# design.net
KiCad netlist of a schematic drawn in Altium Designer
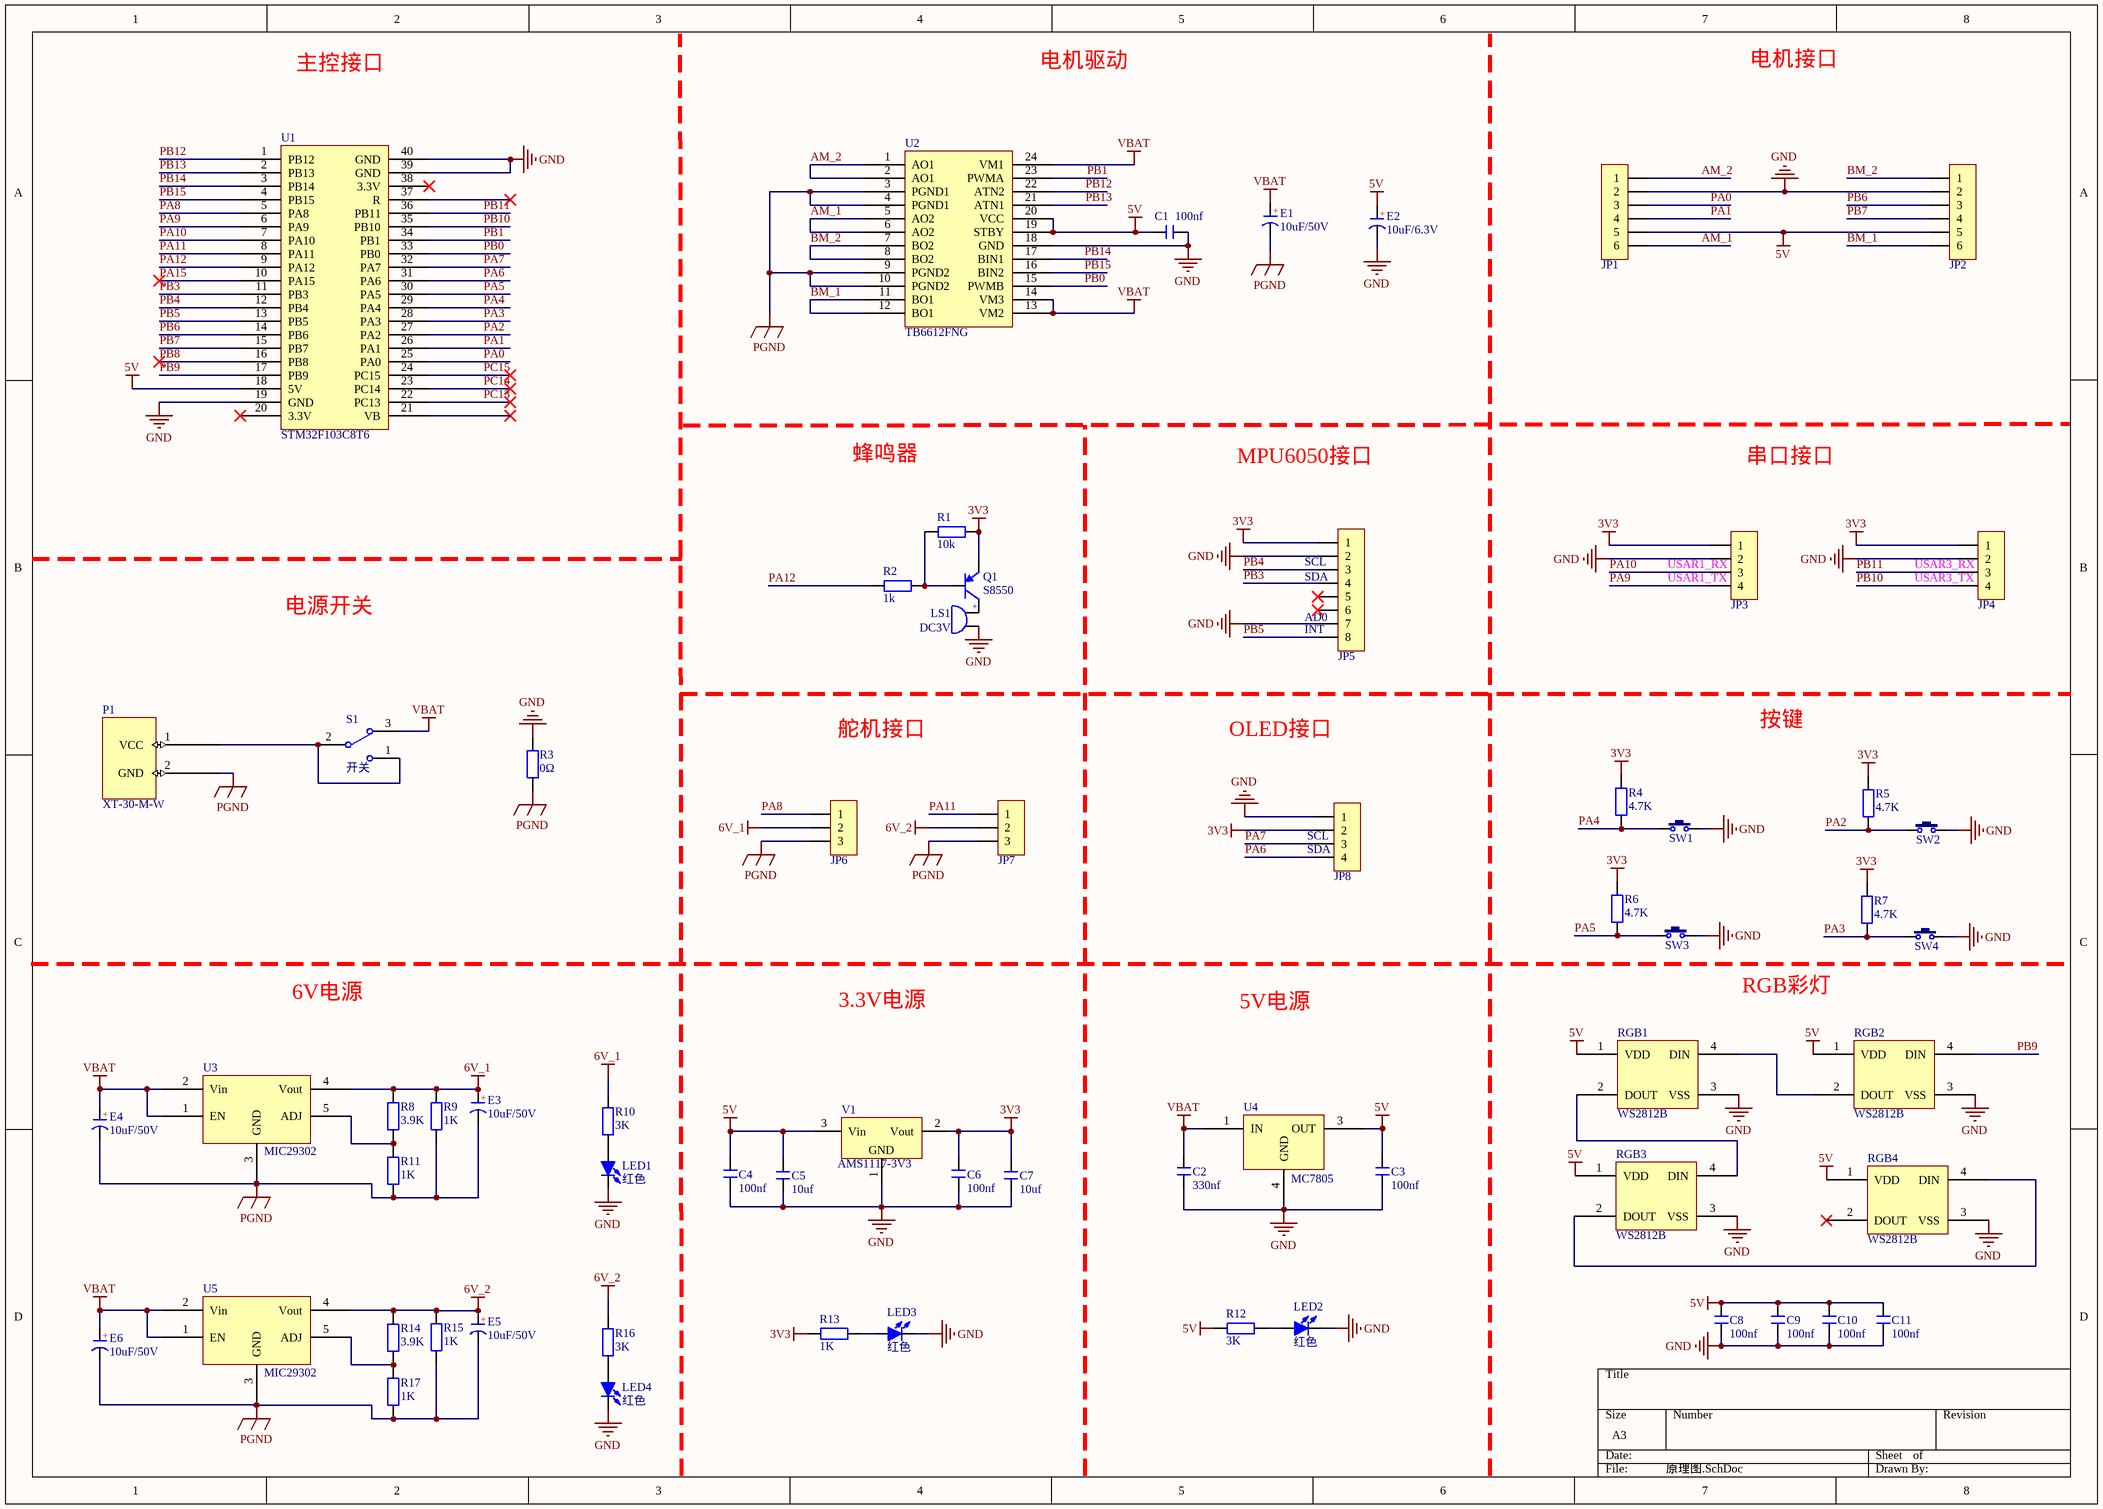
[diagram p0: 原理图.SchDoc]

(export (version "E")
  (design (tool "Eeschema 10.0.6"))
  (components
    (comp (ref "C1")
      (value "100nf")
      (footprint "C 0805_L")
      (description "贴片电容")
      (libsource (lib "0.1 - 电阻-电容-电感") (part "C"))
    )
    (comp (ref "C2")
      (value "330nf")
      (footprint "C 0805_L")
      (description "贴片电容")
      (libsource (lib "0.1 - 电阻-电容-电感") (part "C"))
    )
    (comp (ref "C3")
      (value "100nf")
      (footprint "C 0805_L")
      (description "贴片电容")
      (libsource (lib "0.1 - 电阻-电容-电感") (part "C"))
    )
    (comp (ref "C4")
      (value "100nf")
      (footprint "C 0805_L")
      (description "贴片电容")
      (libsource (lib "0.1 - 电阻-电容-电感") (part "C"))
    )
    (comp (ref "C5")
      (value "10uf")
      (footprint "C 0805_L")
      (description "贴片电容")
      (libsource (lib "0.1 - 电阻-电容-电感") (part "C"))
    )
    (comp (ref "C6")
      (value "100nf")
      (footprint "C 0805_L")
      (description "贴片电容")
      (libsource (lib "0.1 - 电阻-电容-电感") (part "C"))
    )
    (comp (ref "C7")
      (value "10uf")
      (footprint "C 0805_L")
      (description "贴片电容")
      (libsource (lib "0.1 - 电阻-电容-电感") (part "C"))
    )
    (comp (ref "C8")
      (value "100nf")
      (footprint "C 0805_L")
      (description "贴片电容")
      (libsource (lib "0.1 - 电阻-电容-电感") (part "C"))
    )
    (comp (ref "C9")
      (value "100nf")
      (footprint "C 0805_L")
      (description "贴片电容")
      (libsource (lib "0.1 - 电阻-电容-电感") (part "C"))
    )
    (comp (ref "C10")
      (value "100nf")
      (footprint "C 0805_L")
      (description "贴片电容")
      (libsource (lib "0.1 - 电阻-电容-电感") (part "C"))
    )
    (comp (ref "C11")
      (value "100nf")
      (footprint "C 0805_L")
      (description "贴片电容")
      (libsource (lib "0.1 - 电阻-电容-电感") (part "C"))
    )
    (comp (ref "E1")
      (value "10uF/50V")
      (footprint "CM C(5*5.4)")
      (description "贴片电解电容")
      (fields (field (name "版权归属") "封装库来自淘宝 ID：黄晶宝石"))
      (libsource (lib "0.1 - 电阻-电容-电感") (part "CE_SMD"))
    )
    (comp (ref "E2")
      (value "10uF/6.3V")
      (footprint "CD A(3216)")
      (description "贴片钽电容")
      (libsource (lib "0.1 - 电阻-电容-电感") (part "CT"))
    )
    (comp (ref "E3")
      (value "10uF/50V")
      (footprint "CS 2.0*5*8 - V")
      (description "贴片电解电容")
      (fields (field (name "版权归属") "封装库来自淘宝 ID：黄晶宝石"))
      (libsource (lib "0.1 - 电阻-电容-电感") (part "CE_SMD"))
    )
    (comp (ref "E4")
      (value "10uF/50V")
      (footprint "CS 2.0*5*8 - V")
      (description "贴片电解电容")
      (fields (field (name "版权归属") "封装库来自淘宝 ID：黄晶宝石"))
      (libsource (lib "0.1 - 电阻-电容-电感") (part "CE_SMD"))
    )
    (comp (ref "E5")
      (value "10uF/50V")
      (footprint "CS 2.0*5*8 - V")
      (description "贴片电解电容")
      (fields (field (name "版权归属") "封装库来自淘宝 ID：黄晶宝石"))
      (libsource (lib "0.1 - 电阻-电容-电感") (part "CE_SMD"))
    )
    (comp (ref "E6")
      (value "10uF/50V")
      (footprint "CS 2.0*5*8 - V")
      (description "贴片电解电容")
      (fields (field (name "版权归属") "封装库来自淘宝 ID：黄晶宝石"))
      (libsource (lib "0.1 - 电阻-电容-电感") (part "CE_SMD"))
    )
    (comp (ref "JP1")
      (value "HDR-1X6")
      (footprint "XH2.54-WI-6P")
      (description "6P接插件")
      (fields (field (name "版权归属") "封装库来自淘宝 ID：黄晶宝石"))
      (libsource (lib "") (part "Header 6_1"))
    )
    (comp (ref "JP2")
      (value "HDR-1X6")
      (footprint "XH2.54-WI-6P")
      (description "6P接插件")
      (fields (field (name "版权归属") "封装库来自淘宝 ID：黄晶宝石"))
      (libsource (lib "5.3 - 接插件-脚距2.54 (100mil) ") (part "Header 6"))
    )
    (comp (ref "JP3")
      (value "HDR-1X4")
      (footprint "HDR2.54-M-LI-4P")
      (description "4P接插件")
      (fields (field (name "版权归属") "封装库来自淘宝 ID：黄晶宝石"))
      (libsource (lib "5.3 - 接插件-脚距2.54 (100mil) ") (part "Header 4"))
    )
    (comp (ref "JP4")
      (value "HDR-1X4")
      (footprint "HDR2.54-M-LI-4P")
      (description "4P接插件")
      (fields (field (name "版权归属") "封装库来自淘宝 ID：黄晶宝石"))
      (libsource (lib "5.3 - 接插件-脚距2.54 (100mil) ") (part "Header 4"))
    )
    (comp (ref "JP5")
      (value "HDR-1X8")
      (footprint "HDR2.54-M-LI-8P")
      (description "8P接插件")
      (fields (field (name "版权归属") "封装库来自淘宝 ID：黄晶宝石"))
      (libsource (lib "5.3 - 接插件-脚距2.54 (100mil) ") (part "Header 8"))
    )
    (comp (ref "JP6")
      (value "HDR-1X3")
      (footprint "HDR2.54-LI-3P")
      (description "3P接插件")
      (fields (field (name "版权归属") "封装库来自淘宝 ID：黄晶宝石"))
      (libsource (lib "5.3 - 接插件-脚距2.54 (100mil) ") (part "Header 3"))
    )
    (comp (ref "JP7")
      (value "HDR-1X3")
      (footprint "HDR2.54-LI-3P")
      (description "3P接插件")
      (fields (field (name "版权归属") "封装库来自淘宝 ID：黄晶宝石"))
      (libsource (lib "5.3 - 接插件-脚距2.54 (100mil) ") (part "Header 3"))
    )
    (comp (ref "JP8")
      (value "HDR-1X4")
      (footprint "HDR2.54-M-LI-4P")
      (description "4P接插件")
      (fields (field (name "版权归属") "封装库来自淘宝 ID：黄晶宝石"))
      (libsource (lib "5.3 - 接插件-脚距2.54 (100mil) ") (part "Header 4"))
    )
    (comp (ref "LED1")
      (value "红色")
      (footprint "LED 0603B")
      (description "贴片LED")
      (fields (field (name "版权归属") "封装库来自淘宝 ID：黄晶宝石"))
      (libsource (lib "0.3 - LED发光二极管") (part "LED-SMD"))
    )
    (comp (ref "LED2")
      (value "红色")
      (footprint "LED 0603B")
      (description "贴片LED")
      (fields (field (name "版权归属") "封装库来自淘宝 ID：黄晶宝石"))
      (libsource (lib "0.3 - LED发光二极管") (part "LED-SMD"))
    )
    (comp (ref "LED3")
      (value "红色")
      (footprint "LED 0603B")
      (description "贴片LED")
      (fields (field (name "版权归属") "封装库来自淘宝 ID：黄晶宝石"))
      (libsource (lib "0.3 - LED发光二极管") (part "LED-SMD"))
    )
    (comp (ref "LED4")
      (value "红色")
      (footprint "LED 0603B")
      (description "贴片LED")
      (fields (field (name "版权归属") "封装库来自淘宝 ID：黄晶宝石"))
      (libsource (lib "0.3 - LED发光二极管") (part "LED-SMD"))
    )
    (comp (ref "LS1")
      (value "DC3V")
      (footprint "BEEP 5x9x5.5")
      (description "蜂鸣器")
      (fields (field (name "版权归属") "封装库来自淘宝 ID：黄晶宝石"))
      (libsource (lib "4.1 - 未分类器件") (part "BEEP"))
    )
    (comp (ref "P1")
      (value "XT-30-M-W")
      (footprint "XT-30-M-W")
      (description "小电流模型插头XT-30 低阻值香蕉插头_MAX current 30A,公头")
      (libsource (lib "Connect_Compoent") (part "XT-30-M-W"))
    )
    (comp (ref "Q1")
      (value "S8550")
      (footprint "SOT23-3N")
      (description "高频放大-PNP型")
      (fields (field (name "版权归属") "封装库来自淘宝 ID：黄晶宝石"))
      (libsource (lib "0.4 - 三极管") (part "8550-SMD"))
    )
    (comp (ref "R1")
      (value "10k")
      (footprint "R 0805_L")
      (description "贴片电阻")
      (fields (field (name "版权归属") "来自淘宝 ID：黄晶宝石"))
      (libsource (lib "0.1 - 电阻-电容-电感") (part "R"))
    )
    (comp (ref "R2")
      (value "1k")
      (footprint "R 0805_L")
      (description "贴片电阻")
      (fields (field (name "版权归属") "来自淘宝 ID：黄晶宝石"))
      (libsource (lib "0.1 - 电阻-电容-电感") (part "R"))
    )
    (comp (ref "R3")
      (value "0Ω")
      (footprint "R 0805_L")
      (description "贴片电阻")
      (fields (field (name "版权归属") "来自淘宝 ID：黄晶宝石"))
      (libsource (lib "0.1 - 电阻-电容-电感") (part "R"))
    )
    (comp (ref "R4")
      (value "4.7K")
      (footprint "R 0805_L")
      (description "贴片电阻")
      (fields (field (name "版权归属") "来自淘宝 ID：黄晶宝石"))
      (libsource (lib "0.1 - 电阻-电容-电感") (part "R"))
    )
    (comp (ref "R5")
      (value "4.7K")
      (footprint "R 0805_L")
      (description "贴片电阻")
      (fields (field (name "版权归属") "来自淘宝 ID：黄晶宝石"))
      (libsource (lib "0.1 - 电阻-电容-电感") (part "R"))
    )
    (comp (ref "R6")
      (value "4.7K")
      (footprint "R 0805_L")
      (description "贴片电阻")
      (fields (field (name "版权归属") "来自淘宝 ID：黄晶宝石"))
      (libsource (lib "0.1 - 电阻-电容-电感") (part "R"))
    )
    (comp (ref "R7")
      (value "4.7K")
      (footprint "R 0805_L")
      (description "贴片电阻")
      (fields (field (name "版权归属") "来自淘宝 ID：黄晶宝石"))
      (libsource (lib "0.1 - 电阻-电容-电感") (part "R"))
    )
    (comp (ref "R8")
      (value "3.9K")
      (footprint "R 0805_L")
      (description "贴片电阻")
      (fields (field (name "版权归属") "来自淘宝 ID：黄晶宝石"))
      (libsource (lib "0.1 - 电阻-电容-电感") (part "R"))
    )
    (comp (ref "R9")
      (value "1K")
      (footprint "R 0805_L")
      (description "贴片电阻")
      (fields (field (name "版权归属") "来自淘宝 ID：黄晶宝石"))
      (libsource (lib "0.1 - 电阻-电容-电感") (part "R"))
    )
    (comp (ref "R10")
      (value "3K")
      (footprint "R 0805_L")
      (description "贴片电阻")
      (fields (field (name "版权归属") "来自淘宝 ID：黄晶宝石"))
      (libsource (lib "0.1 - 电阻-电容-电感") (part "R"))
    )
    (comp (ref "R11")
      (value "1K")
      (footprint "R 0805_L")
      (description "贴片电阻")
      (fields (field (name "版权归属") "来自淘宝 ID：黄晶宝石"))
      (libsource (lib "0.1 - 电阻-电容-电感") (part "R"))
    )
    (comp (ref "R12")
      (value "3K")
      (footprint "R 0805_L")
      (description "贴片电阻")
      (fields (field (name "版权归属") "来自淘宝 ID：黄晶宝石"))
      (libsource (lib "0.1 - 电阻-电容-电感") (part "R"))
    )
    (comp (ref "R13")
      (value "1K")
      (footprint "R 0805_L")
      (description "贴片电阻")
      (fields (field (name "版权归属") "来自淘宝 ID：黄晶宝石"))
      (libsource (lib "0.1 - 电阻-电容-电感") (part "R"))
    )
    (comp (ref "R14")
      (value "3.9K")
      (footprint "R 0805_L")
      (description "贴片电阻")
      (fields (field (name "版权归属") "来自淘宝 ID：黄晶宝石"))
      (libsource (lib "0.1 - 电阻-电容-电感") (part "R"))
    )
    (comp (ref "R15")
      (value "1K")
      (footprint "R 0805_L")
      (description "贴片电阻")
      (fields (field (name "版权归属") "来自淘宝 ID：黄晶宝石"))
      (libsource (lib "0.1 - 电阻-电容-电感") (part "R"))
    )
    (comp (ref "R16")
      (value "3K")
      (footprint "R 0805_L")
      (description "贴片电阻")
      (fields (field (name "版权归属") "来自淘宝 ID：黄晶宝石"))
      (libsource (lib "0.1 - 电阻-电容-电感") (part "R"))
    )
    (comp (ref "R17")
      (value "1K")
      (footprint "R 0805_L")
      (description "贴片电阻")
      (fields (field (name "版权归属") "来自淘宝 ID：黄晶宝石"))
      (libsource (lib "0.1 - 电阻-电容-电感") (part "R"))
    )
    (comp (ref "RGB1")
      (value "WS2812B")
      (footprint "WS2812B")
      (libsource (lib "071Schlib1") (part "RGB_WS2812B_4Pin"))
    )
    (comp (ref "RGB2")
      (value "WS2812B")
      (footprint "WS2812B")
      (libsource (lib "071Schlib1") (part "RGB_WS2812B_4Pin"))
    )
    (comp (ref "RGB3")
      (value "WS2812B")
      (footprint "WS2812B")
      (libsource (lib "071Schlib1") (part "RGB_WS2812B_4Pin"))
    )
    (comp (ref "RGB4")
      (value "WS2812B")
      (footprint "WS2812B")
      (libsource (lib "071Schlib1") (part "RGB_WS2812B_4Pin"))
    )
    (comp (ref "S1") (value "开关") (footprint "MTS-10x") (libsource (lib "开关元件库") (part "拨动开关（三脚）")))
    (comp (ref "SW1")
      (value "3x6x5")
      (footprint "TSW SMD-3*6*2.5")
      (description "3x6轻触开关")
      (fields (field (name "版权归属") "封装库来自淘宝 ID：黄晶宝石"))
      (libsource (lib "0.7 - 常用按键-开关") (part "TSW 3x6"))
    )
    (comp (ref "SW2")
      (value "3x6x5")
      (footprint "TSW SMD-3*6*2.5")
      (description "3x6轻触开关")
      (fields (field (name "版权归属") "封装库来自淘宝 ID：黄晶宝石"))
      (libsource (lib "0.7 - 常用按键-开关") (part "TSW 3x6"))
    )
    (comp (ref "SW3")
      (value "3x6x5")
      (footprint "TSW SMD-3*6*2.5")
      (description "3x6轻触开关")
      (fields (field (name "版权归属") "封装库来自淘宝 ID：黄晶宝石"))
      (libsource (lib "0.7 - 常用按键-开关") (part "TSW 3x6"))
    )
    (comp (ref "SW4")
      (value "3x6x5")
      (footprint "TSW SMD-3*6*2.5")
      (description "3x6轻触开关")
      (fields (field (name "版权归属") "封装库来自淘宝 ID：黄晶宝石"))
      (libsource (lib "0.7 - 常用按键-开关") (part "TSW 3x6"))
    )
    (comp (ref "U1")
      (value "STM32F103C8T6")
      (footprint "STM32F103C8T6最小系统板3")
      (libsource (lib "071Schlib1") (part "STM32F103C8T6最小系统板"))
    )
    (comp (ref "U2")
      (value "TB6612FNG")
      (footprint "SSOP24_L")
      (libsource (lib "071Schlib1") (part "TB6612FNG"))
    )
    (comp (ref "U3")
      (value "MIC29302")
      (footprint "TO-263-5")
      (libsource (lib "071Schlib1") (part "MIC29302"))
    )
    (comp (ref "U4") (value "MC7805") (footprint "TO-263-3") (libsource (lib "071Schlib1") (part "MC7805")))
    (comp (ref "U5")
      (value "MIC29302")
      (footprint "TO-263-5")
      (libsource (lib "071Schlib1") (part "MIC29302"))
    )
    (comp (ref "V1")
      (value "AMS1117-3V3")
      (footprint "SOT223_L")
      (description "三端稳压芯片")
      (libsource (lib "1.1 - 电源类芯片") (part "AMS1117"))
    )
  )
  (nets
    (net (code "1") (name "/AM_1") (class "Default")
      (node (ref "JP1") (pin "6") (pinfunction "6_6") (pintype "passive"))
      (node (ref "U2") (pin "5") (pinfunction "AO2_5") (pintype "passive"))
      (node (ref "U2") (pin "6") (pinfunction "AO2_6") (pintype "passive"))
    )
    (net (code "2") (name "/AM_2") (class "Default")
      (node (ref "JP1") (pin "1") (pinfunction "1_1") (pintype "passive"))
      (node (ref "U2") (pin "1") (pinfunction "AO1_1") (pintype "passive"))
      (node (ref "U2") (pin "2") (pinfunction "AO1_2") (pintype "passive"))
    )
    (net (code "3") (name "/BM_1") (class "Default")
      (node (ref "JP2") (pin "6") (pinfunction "6_6") (pintype "passive"))
      (node (ref "U2") (pin "11") (pinfunction "BO1_11") (pintype "passive"))
      (node (ref "U2") (pin "12") (pinfunction "BO1_12") (pintype "passive"))
    )
    (net (code "4") (name "/BM_2") (class "Default")
      (node (ref "JP2") (pin "1") (pinfunction "1_1") (pintype "passive"))
      (node (ref "U2") (pin "7") (pinfunction "BO2_7") (pintype "passive"))
      (node (ref "U2") (pin "8") (pinfunction "BO2_8") (pintype "passive"))
    )
    (net (code "5") (name "/PA0") (class "Default")
      (node (ref "JP1") (pin "3") (pinfunction "3_3") (pintype "passive"))
      (node (ref "U1") (pin "25") (pinfunction "PA0_25") (pintype "passive"))
    )
    (net (code "6") (name "/PA1") (class "Default")
      (node (ref "JP1") (pin "4") (pinfunction "4_4") (pintype "passive"))
      (node (ref "U1") (pin "26") (pinfunction "PA1_26") (pintype "passive"))
    )
    (net (code "7") (name "/PA2") (class "Default")
      (node (ref "R5") (pin "2") (pinfunction "2_2") (pintype "passive"))
      (node (ref "SW2") (pin "1") (pinfunction "1_1") (pintype "passive"))
      (node (ref "U1") (pin "27") (pinfunction "PA2_27") (pintype "passive"))
    )
    (net (code "8") (name "/PA3") (class "Default")
      (node (ref "R7") (pin "2") (pinfunction "2_2") (pintype "passive"))
      (node (ref "SW4") (pin "1") (pinfunction "1_1") (pintype "passive"))
      (node (ref "U1") (pin "28") (pinfunction "PA3_28") (pintype "passive"))
    )
    (net (code "9") (name "/PA4") (class "Default")
      (node (ref "R4") (pin "2") (pinfunction "2_2") (pintype "passive"))
      (node (ref "SW1") (pin "1") (pinfunction "1_1") (pintype "passive"))
      (node (ref "U1") (pin "29") (pinfunction "PA4_29") (pintype "passive"))
    )
    (net (code "10") (name "/PA5") (class "Default")
      (node (ref "R6") (pin "2") (pinfunction "2_2") (pintype "passive"))
      (node (ref "SW3") (pin "1") (pinfunction "1_1") (pintype "passive"))
      (node (ref "U1") (pin "30") (pinfunction "PA5_30") (pintype "passive"))
    )
    (net (code "11") (name "/PA6") (class "Default")
      (node (ref "JP8") (pin "4") (pinfunction "4_4") (pintype "passive"))
      (node (ref "U1") (pin "31") (pinfunction "PA6_31") (pintype "passive"))
    )
    (net (code "12") (name "/PA7") (class "Default")
      (node (ref "JP8") (pin "3") (pinfunction "3_3") (pintype "passive"))
      (node (ref "U1") (pin "32") (pinfunction "PA7_32") (pintype "passive"))
    )
    (net (code "13") (name "/PA8") (class "Default")
      (node (ref "JP6") (pin "1") (pinfunction "1_1") (pintype "passive"))
      (node (ref "U1") (pin "5") (pinfunction "PA8_5") (pintype "passive"))
    )
    (net (code "14") (name "/PA9") (class "Default")
      (node (ref "JP3") (pin "4") (pinfunction "4_4") (pintype "passive"))
      (node (ref "U1") (pin "6") (pinfunction "PA9_6") (pintype "passive"))
    )
    (net (code "15") (name "/PA10") (class "Default")
      (node (ref "JP3") (pin "3") (pinfunction "3_3") (pintype "passive"))
      (node (ref "U1") (pin "7") (pinfunction "PA10_7") (pintype "passive"))
    )
    (net (code "16") (name "/PA11") (class "Default")
      (node (ref "JP7") (pin "1") (pinfunction "1_1") (pintype "passive"))
      (node (ref "U1") (pin "8") (pinfunction "PA11_8") (pintype "passive"))
    )
    (net (code "17") (name "/PA12") (class "Default")
      (node (ref "R2") (pin "1") (pinfunction "1_1") (pintype "passive"))
      (node (ref "U1") (pin "9") (pinfunction "PA12_9") (pintype "passive"))
    )
    (net (code "18") (name "/PA15") (class "Default")
      (node (ref "U1") (pin "10") (pinfunction "PA15_10") (pintype "passive+no_connect"))
    )
    (net (code "19") (name "/PB0") (class "Default")
      (node (ref "U1") (pin "33") (pinfunction "PB0_33") (pintype "passive"))
      (node (ref "U2") (pin "15") (pinfunction "PWMB_15") (pintype "passive"))
    )
    (net (code "20") (name "/PB1") (class "Default")
      (node (ref "U1") (pin "34") (pinfunction "PB1_34") (pintype "passive"))
      (node (ref "U2") (pin "23") (pinfunction "PWMA_23") (pintype "passive"))
    )
    (net (code "21") (name "/PB3") (class "Default")
      (node (ref "JP5") (pin "4") (pinfunction "4_4") (pintype "passive"))
      (node (ref "U1") (pin "11") (pinfunction "PB3_11") (pintype "passive"))
    )
    (net (code "22") (name "/PB4") (class "Default")
      (node (ref "JP5") (pin "3") (pinfunction "3_3") (pintype "passive"))
      (node (ref "U1") (pin "12") (pinfunction "PB4_12") (pintype "passive"))
    )
    (net (code "23") (name "/PB5") (class "Default")
      (node (ref "JP5") (pin "8") (pinfunction "8_8") (pintype "passive"))
      (node (ref "U1") (pin "13") (pinfunction "PB5_13") (pintype "passive"))
    )
    (net (code "24") (name "/PB6") (class "Default")
      (node (ref "JP2") (pin "3") (pinfunction "3_3") (pintype "passive"))
      (node (ref "U1") (pin "14") (pinfunction "PB6_14") (pintype "passive"))
    )
    (net (code "25") (name "/PB7") (class "Default")
      (node (ref "JP2") (pin "4") (pinfunction "4_4") (pintype "passive"))
      (node (ref "U1") (pin "15") (pinfunction "PB7_15") (pintype "passive"))
    )
    (net (code "26") (name "/PB8") (class "Default")
      (node (ref "U1") (pin "16") (pinfunction "PB8_16") (pintype "passive+no_connect"))
    )
    (net (code "27") (name "/PB9") (class "Default")
      (node (ref "RGB2") (pin "4") (pinfunction "DIN_4") (pintype "passive"))
      (node (ref "U1") (pin "17") (pinfunction "PB9_17") (pintype "passive"))
    )
    (net (code "28") (name "/PB10") (class "Default")
      (node (ref "JP4") (pin "4") (pinfunction "4_4") (pintype "passive"))
      (node (ref "U1") (pin "35") (pinfunction "PB10_35") (pintype "passive"))
    )
    (net (code "29") (name "/PB11") (class "Default")
      (node (ref "JP4") (pin "3") (pinfunction "3_3") (pintype "passive"))
      (node (ref "U1") (pin "36") (pinfunction "PB11_36") (pintype "passive"))
    )
    (net (code "30") (name "/PB12") (class "Default")
      (node (ref "U1") (pin "1") (pinfunction "PB12_1") (pintype "passive"))
      (node (ref "U2") (pin "22") (pinfunction "ATN2_22") (pintype "passive"))
    )
    (net (code "31") (name "/PB13") (class "Default")
      (node (ref "U1") (pin "2") (pinfunction "PB13_2") (pintype "passive"))
      (node (ref "U2") (pin "21") (pinfunction "ATN1_21") (pintype "passive"))
    )
    (net (code "32") (name "/PB14") (class "Default")
      (node (ref "U1") (pin "3") (pinfunction "PB14_3") (pintype "passive"))
      (node (ref "U2") (pin "17") (pinfunction "BIN1_17") (pintype "passive"))
    )
    (net (code "33") (name "/PB15") (class "Default")
      (node (ref "U1") (pin "4") (pinfunction "PB15_4") (pintype "passive"))
      (node (ref "U2") (pin "16") (pinfunction "BIN2_16") (pintype "passive"))
    )
    (net (code "34") (name "/PC13") (class "Default")
      (node (ref "U1") (pin "22") (pinfunction "PC13_22") (pintype "passive+no_connect"))
    )
    (net (code "35") (name "/PC14") (class "Default")
      (node (ref "U1") (pin "23") (pinfunction "PC14_23") (pintype "passive+no_connect"))
    )
    (net (code "36") (name "/PC15") (class "Default")
      (node (ref "U1") (pin "24") (pinfunction "PC15_24") (pintype "passive+no_connect"))
    )
    (net (code "37") (name "3V3") (class "Default")
      (node (ref "C6") (pin "2") (pinfunction "2_2") (pintype "passive"))
      (node (ref "C7") (pin "2") (pinfunction "2_2") (pintype "passive"))
      (node (ref "JP3") (pin "1") (pinfunction "1_1") (pintype "passive"))
      (node (ref "JP4") (pin "1") (pinfunction "1_1") (pintype "passive"))
      (node (ref "JP5") (pin "1") (pinfunction "1_1") (pintype "passive"))
      (node (ref "JP8") (pin "2") (pinfunction "2_2") (pintype "passive"))
      (node (ref "Q1") (pin "2") (pinfunction "E_2") (pintype "passive"))
      (node (ref "R1") (pin "1") (pinfunction "1_1") (pintype "passive"))
      (node (ref "R13") (pin "1") (pinfunction "1_1") (pintype "passive"))
      (node (ref "R4") (pin "1") (pinfunction "1_1") (pintype "passive"))
      (node (ref "R5") (pin "1") (pinfunction "1_1") (pintype "passive"))
      (node (ref "R6") (pin "1") (pinfunction "1_1") (pintype "passive"))
      (node (ref "R7") (pin "1") (pinfunction "1_1") (pintype "passive"))
      (node (ref "V1") (pin "2") (pinfunction "Vout_2") (pintype "passive"))
    )
    (net (code "38") (name "5V") (class "Default")
      (node (ref "C1") (pin "2") (pinfunction "2_2") (pintype "passive"))
      (node (ref "C10") (pin "2") (pinfunction "2_2") (pintype "passive"))
      (node (ref "C11") (pin "2") (pinfunction "2_2") (pintype "passive"))
      (node (ref "C3") (pin "2") (pinfunction "2_2") (pintype "passive"))
      (node (ref "C4") (pin "2") (pinfunction "2_2") (pintype "passive"))
      (node (ref "C5") (pin "2") (pinfunction "2_2") (pintype "passive"))
      (node (ref "C8") (pin "2") (pinfunction "2_2") (pintype "passive"))
      (node (ref "C9") (pin "2") (pinfunction "2_2") (pintype "passive"))
      (node (ref "E2") (pin "1") (pinfunction "A_1") (pintype "passive"))
      (node (ref "JP1") (pin "5") (pinfunction "5_5") (pintype "passive"))
      (node (ref "JP2") (pin "5") (pinfunction "5_5") (pintype "passive"))
      (node (ref "R12") (pin "1") (pinfunction "1_1") (pintype "passive"))
      (node (ref "RGB1") (pin "1") (pinfunction "VDD_1") (pintype "passive"))
      (node (ref "RGB2") (pin "1") (pinfunction "VDD_1") (pintype "passive"))
      (node (ref "RGB3") (pin "1") (pinfunction "VDD_1") (pintype "passive"))
      (node (ref "RGB4") (pin "1") (pinfunction "VDD_1") (pintype "passive"))
      (node (ref "U1") (pin "18") (pinfunction "5V_18") (pintype "passive"))
      (node (ref "U2") (pin "19") (pinfunction "STBY_19") (pintype "passive"))
      (node (ref "U2") (pin "20") (pinfunction "VCC_20") (pintype "passive"))
      (node (ref "U4") (pin "3") (pinfunction "OUT_3") (pintype "passive"))
      (node (ref "V1") (pin "3") (pinfunction "Vin_3") (pintype "passive"))
    )
    (net (code "39") (name "6V_1") (class "Default")
      (node (ref "E3") (pin "1") (pinfunction "A_1") (pintype "passive"))
      (node (ref "JP6") (pin "2") (pinfunction "2_2") (pintype "passive"))
      (node (ref "R10") (pin "1") (pinfunction "1_1") (pintype "passive"))
      (node (ref "R8") (pin "1") (pinfunction "1_1") (pintype "passive"))
      (node (ref "R9") (pin "1") (pinfunction "1_1") (pintype "passive"))
      (node (ref "U3") (pin "4") (pinfunction "Vout_4") (pintype "passive"))
    )
    (net (code "40") (name "6V_2") (class "Default")
      (node (ref "E5") (pin "1") (pinfunction "A_1") (pintype "passive"))
      (node (ref "JP7") (pin "2") (pinfunction "2_2") (pintype "passive"))
      (node (ref "R14") (pin "1") (pinfunction "1_1") (pintype "passive"))
      (node (ref "R15") (pin "1") (pinfunction "1_1") (pintype "passive"))
      (node (ref "R16") (pin "1") (pinfunction "1_1") (pintype "passive"))
      (node (ref "U5") (pin "4") (pinfunction "Vout_4") (pintype "passive"))
    )
    (net (code "41") (name "GND") (class "Default")
      (node (ref "C1") (pin "1") (pinfunction "1_1") (pintype "passive"))
      (node (ref "C10") (pin "1") (pinfunction "1_1") (pintype "passive"))
      (node (ref "C11") (pin "1") (pinfunction "1_1") (pintype "passive"))
      (node (ref "C2") (pin "1") (pinfunction "1_1") (pintype "passive"))
      (node (ref "C3") (pin "1") (pinfunction "1_1") (pintype "passive"))
      (node (ref "C4") (pin "1") (pinfunction "1_1") (pintype "passive"))
      (node (ref "C5") (pin "1") (pinfunction "1_1") (pintype "passive"))
      (node (ref "C6") (pin "1") (pinfunction "1_1") (pintype "passive"))
      (node (ref "C7") (pin "1") (pinfunction "1_1") (pintype "passive"))
      (node (ref "C8") (pin "1") (pinfunction "1_1") (pintype "passive"))
      (node (ref "C9") (pin "1") (pinfunction "1_1") (pintype "passive"))
      (node (ref "E2") (pin "2") (pinfunction "K_2") (pintype "passive"))
      (node (ref "JP1") (pin "2") (pinfunction "2_2") (pintype "passive"))
      (node (ref "JP2") (pin "2") (pinfunction "2_2") (pintype "passive"))
      (node (ref "JP3") (pin "2") (pinfunction "2_2") (pintype "passive"))
      (node (ref "JP4") (pin "2") (pinfunction "2_2") (pintype "passive"))
      (node (ref "JP5") (pin "2") (pinfunction "2_2") (pintype "passive"))
      (node (ref "JP5") (pin "7") (pinfunction "7_7") (pintype "passive"))
      (node (ref "JP8") (pin "1") (pinfunction "1_1") (pintype "passive"))
      (node (ref "LED1") (pin "2") (pinfunction "K_2") (pintype "passive"))
      (node (ref "LED2") (pin "2") (pinfunction "K_2") (pintype "passive"))
      (node (ref "LED3") (pin "2") (pinfunction "K_2") (pintype "passive"))
      (node (ref "LED4") (pin "2") (pinfunction "K_2") (pintype "passive"))
      (node (ref "LS1") (pin "2") (pinfunction "2_2") (pintype "passive"))
      (node (ref "R3") (pin "2") (pinfunction "2_2") (pintype "passive"))
      (node (ref "RGB1") (pin "3") (pinfunction "VSS_3") (pintype "passive"))
      (node (ref "RGB2") (pin "3") (pinfunction "VSS_3") (pintype "passive"))
      (node (ref "RGB3") (pin "3") (pinfunction "VSS_3") (pintype "passive"))
      (node (ref "RGB4") (pin "3") (pinfunction "VSS_3") (pintype "passive"))
      (node (ref "SW1") (pin "2") (pinfunction "2_2") (pintype "passive"))
      (node (ref "SW2") (pin "2") (pinfunction "2_2") (pintype "passive"))
      (node (ref "SW3") (pin "2") (pinfunction "2_2") (pintype "passive"))
      (node (ref "SW4") (pin "2") (pinfunction "2_2") (pintype "passive"))
      (node (ref "U1") (pin "19") (pinfunction "GND_19") (pintype "passive"))
      (node (ref "U1") (pin "39") (pinfunction "GND_39") (pintype "passive"))
      (node (ref "U1") (pin "40") (pinfunction "GND_40") (pintype "passive"))
      (node (ref "U2") (pin "18") (pinfunction "GND_18") (pintype "passive"))
      (node (ref "U4") (pin "4") (pinfunction "GND_4") (pintype "passive"))
      (node (ref "V1") (pin "1") (pinfunction "GND_1") (pintype "passive"))
    )
    (net (code "42") (name "Net-(LED1-A)") (class "Default")
      (node (ref "LED1") (pin "1") (pinfunction "A_1") (pintype "passive"))
      (node (ref "R10") (pin "2") (pinfunction "2_2") (pintype "passive"))
    )
    (net (code "43") (name "Net-(LED2-A)") (class "Default")
      (node (ref "LED2") (pin "1") (pinfunction "A_1") (pintype "passive"))
      (node (ref "R12") (pin "2") (pinfunction "2_2") (pintype "passive"))
    )
    (net (code "44") (name "Net-(LED3-A)") (class "Default")
      (node (ref "LED3") (pin "1") (pinfunction "A_1") (pintype "passive"))
      (node (ref "R13") (pin "2") (pinfunction "2_2") (pintype "passive"))
    )
    (net (code "45") (name "Net-(LED4-A)") (class "Default")
      (node (ref "LED4") (pin "1") (pinfunction "A_1") (pintype "passive"))
      (node (ref "R16") (pin "2") (pinfunction "2_2") (pintype "passive"))
    )
    (net (code "46") (name "Net-(P1-VCC)") (class "Default")
      (node (ref "P1") (pin "1") (pinfunction "VCC_1") (pintype "bidirectional"))
      (node (ref "S1") (pin "1") (pinfunction "1_1") (pintype "passive"))
      (node (ref "S1") (pin "2") (pinfunction "2_2") (pintype "passive"))
    )
    (net (code "47") (name "Net-(Q1-B)") (class "Default")
      (node (ref "Q1") (pin "1") (pinfunction "B_1") (pintype "passive"))
      (node (ref "R1") (pin "2") (pinfunction "2_2") (pintype "passive"))
      (node (ref "R2") (pin "2") (pinfunction "2_2") (pintype "passive"))
    )
    (net (code "48") (name "Net-(Q1-C)") (class "Default")
      (node (ref "LS1") (pin "1") (pinfunction "1_1") (pintype "passive"))
      (node (ref "Q1") (pin "3") (pinfunction "C_3") (pintype "passive"))
    )
    (net (code "49") (name "Net-(RGB1-DIN)") (class "Default")
      (node (ref "RGB1") (pin "4") (pinfunction "DIN_4") (pintype "passive"))
      (node (ref "RGB2") (pin "2") (pinfunction "DOUT_2") (pintype "passive"))
    )
    (net (code "50") (name "Net-(RGB1-DOUT)") (class "Default")
      (node (ref "RGB1") (pin "2") (pinfunction "DOUT_2") (pintype "passive"))
      (node (ref "RGB3") (pin "4") (pinfunction "DIN_4") (pintype "passive"))
    )
    (net (code "51") (name "Net-(RGB3-DOUT)") (class "Default")
      (node (ref "RGB3") (pin "2") (pinfunction "DOUT_2") (pintype "passive"))
      (node (ref "RGB4") (pin "4") (pinfunction "DIN_4") (pintype "passive"))
    )
    (net (code "52") (name "Net-(U3-ADJ)") (class "Default")
      (node (ref "R11") (pin "2") (pinfunction "2_2") (pintype "passive"))
      (node (ref "R8") (pin "2") (pinfunction "2_2") (pintype "passive"))
      (node (ref "U3") (pin "5") (pinfunction "ADJ_5") (pintype "passive"))
    )
    (net (code "53") (name "Net-(U5-ADJ)") (class "Default")
      (node (ref "R14") (pin "2") (pinfunction "2_2") (pintype "passive"))
      (node (ref "R17") (pin "2") (pinfunction "2_2") (pintype "passive"))
      (node (ref "U5") (pin "5") (pinfunction "ADJ_5") (pintype "passive"))
    )
    (net (code "54") (name "PGND") (class "Default")
      (node (ref "E1") (pin "2") (pinfunction "K_2") (pintype "passive"))
      (node (ref "E3") (pin "2") (pinfunction "K_2") (pintype "passive"))
      (node (ref "E4") (pin "2") (pinfunction "K_2") (pintype "passive"))
      (node (ref "E5") (pin "2") (pinfunction "K_2") (pintype "passive"))
      (node (ref "E6") (pin "2") (pinfunction "K_2") (pintype "passive"))
      (node (ref "JP6") (pin "3") (pinfunction "3_3") (pintype "passive"))
      (node (ref "JP7") (pin "3") (pinfunction "3_3") (pintype "passive"))
      (node (ref "P1") (pin "2") (pinfunction "GND_2") (pintype "bidirectional"))
      (node (ref "R11") (pin "1") (pinfunction "1_1") (pintype "passive"))
      (node (ref "R15") (pin "2") (pinfunction "2_2") (pintype "passive"))
      (node (ref "R17") (pin "1") (pinfunction "1_1") (pintype "passive"))
      (node (ref "R3") (pin "1") (pinfunction "1_1") (pintype "passive"))
      (node (ref "R9") (pin "2") (pinfunction "2_2") (pintype "passive"))
      (node (ref "U2") (pin "10") (pinfunction "PGND2_10") (pintype "passive"))
      (node (ref "U2") (pin "3") (pinfunction "PGND1_3") (pintype "passive"))
      (node (ref "U2") (pin "4") (pinfunction "PGND1_4") (pintype "passive"))
      (node (ref "U2") (pin "9") (pinfunction "PGND2_9") (pintype "passive"))
      (node (ref "U3") (pin "3") (pinfunction "GND_3") (pintype "passive"))
      (node (ref "U5") (pin "3") (pinfunction "GND_3") (pintype "passive"))
    )
    (net (code "55") (name "VBAT") (class "Default")
      (node (ref "C2") (pin "2") (pinfunction "2_2") (pintype "passive"))
      (node (ref "E1") (pin "1") (pinfunction "A_1") (pintype "passive"))
      (node (ref "E4") (pin "1") (pinfunction "A_1") (pintype "passive"))
      (node (ref "E6") (pin "1") (pinfunction "A_1") (pintype "passive"))
      (node (ref "S1") (pin "3") (pinfunction "3_3") (pintype "passive"))
      (node (ref "U2") (pin "13") (pinfunction "VM2_13") (pintype "passive"))
      (node (ref "U2") (pin "14") (pinfunction "VM3_14") (pintype "passive"))
      (node (ref "U2") (pin "24") (pinfunction "VM1_24") (pintype "passive"))
      (node (ref "U3") (pin "1") (pinfunction "EN_1") (pintype "passive"))
      (node (ref "U3") (pin "2") (pinfunction "Vin_2") (pintype "passive"))
      (node (ref "U4") (pin "1") (pinfunction "IN_1") (pintype "passive"))
      (node (ref "U5") (pin "1") (pinfunction "EN_1") (pintype "passive"))
      (node (ref "U5") (pin "2") (pinfunction "Vin_2") (pintype "passive"))
    )
    (net (code "56") (name "unconnected-(JP5-Pad5)") (class "Default")
      (node (ref "JP5") (pin "5") (pinfunction "5_5") (pintype "passive+no_connect"))
    )
    (net (code "57") (name "unconnected-(JP5-Pad6)") (class "Default")
      (node (ref "JP5") (pin "6") (pinfunction "6_6") (pintype "passive+no_connect"))
    )
    (net (code "58") (name "unconnected-(RGB4-DOUT-Pad2)") (class "Default")
      (node (ref "RGB4") (pin "2") (pinfunction "DOUT_2") (pintype "passive+no_connect"))
    )
    (net (code "59") (name "unconnected-(U1-3.3V-Pad20)") (class "Default")
      (node (ref "U1") (pin "20") (pinfunction "3.3V_20") (pintype "passive+no_connect"))
    )
    (net (code "60") (name "unconnected-(U1-3.3V-Pad38)") (class "Default")
      (node (ref "U1") (pin "38") (pinfunction "3.3V_38") (pintype "passive+no_connect"))
    )
    (net (code "61") (name "unconnected-(U1-R-Pad37)") (class "Default")
      (node (ref "U1") (pin "37") (pinfunction "R_37") (pintype "passive+no_connect"))
    )
    (net (code "62") (name "unconnected-(U1-VB-Pad21)") (class "Default")
      (node (ref "U1") (pin "21") (pinfunction "VB_21") (pintype "passive+no_connect"))
    )
  )
)
